# DrMcn.net
KiCad netlist of a schematic drawn in EAGLE
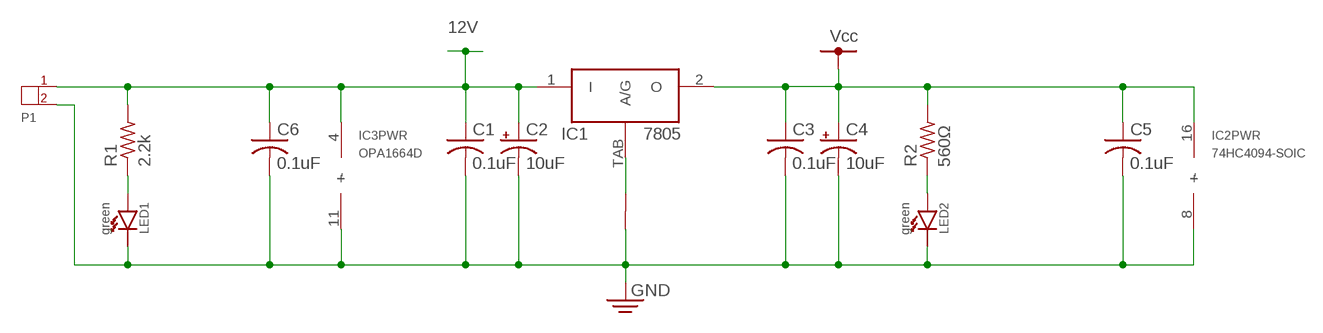
[diagram p0: schematic, sheet 1]
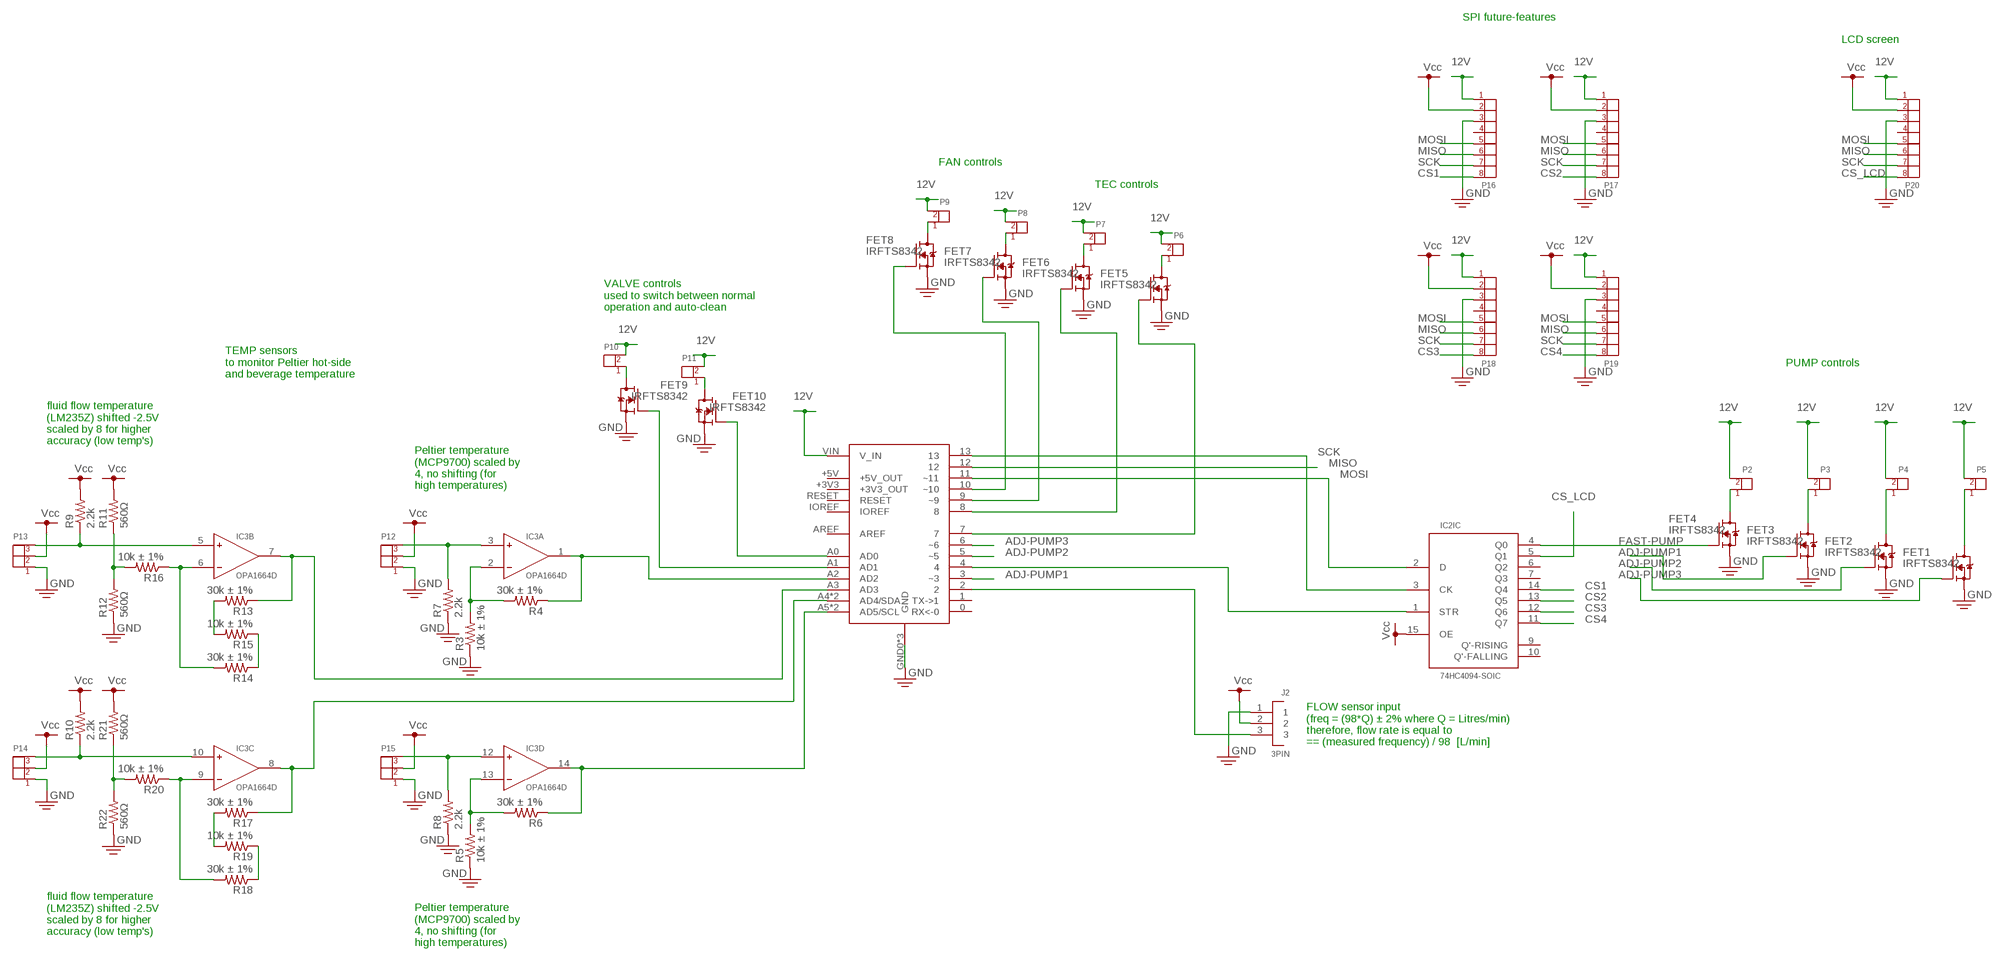
[diagram p1: schematic, sheet 2]

(export (version "E")
  (design (tool "Eeschema 10.0.6"))
  (components
    (comp (ref "-1")
      (value "SEPERATOR")
      (footprint "eagle-import:SEPERATOR")
      (libsource (lib "eagle-import") (part "SEPERATOR"))
    )
    (comp (ref "C1")
      (value "0.1uF")
      (footprint "eagle-import:C0805")
      (libsource (lib "eagle-import") (part "C-USC0805"))
    )
    (comp (ref "C2")
      (value "10uF")
      (footprint "eagle-import:E5-10,5")
      (libsource (lib "eagle-import") (part "CPOL-USE5-10.5"))
    )
    (comp (ref "C3")
      (value "0.1uF")
      (footprint "eagle-import:C0805")
      (libsource (lib "eagle-import") (part "C-USC0805"))
    )
    (comp (ref "C4")
      (value "10uF")
      (footprint "eagle-import:E5-10,5")
      (libsource (lib "eagle-import") (part "CPOL-USE5-10.5"))
    )
    (comp (ref "C5")
      (value "0.1uF")
      (footprint "eagle-import:C0805")
      (libsource (lib "eagle-import") (part "C-USC0805"))
    )
    (comp (ref "C6")
      (value "0.1uF")
      (footprint "eagle-import:C0805")
      (libsource (lib "eagle-import") (part "C-USC0805"))
    )
    (comp (ref "IC1")
      (value "7805")
      (footprint "eagle-import:TO-252")
      (libsource (lib "eagle-import") (part "7805"))
    )
    (comp (ref "IC2")
      (value "74HC4094-SOIC")
      (footprint "eagle-import:16-SOIC")
      (libsource (lib "eagle-import") (part "74HC4094-SOIC"))
    )
    (comp (ref "IC3")
      (value "OPA1664D")
      (footprint "eagle-import:14-SOP")
      (libsource (lib "eagle-import") (part "OPA1664D"))
    )
    (comp (ref "LED1")
      (value "green")
      (footprint "eagle-import:0603-LED")
      (libsource (lib "eagle-import") (part "LG_Q971"))
    )
    (comp (ref "LED2")
      (value "green")
      (footprint "eagle-import:0603-LED")
      (libsource (lib "eagle-import") (part "LG_Q971"))
    )
    (comp (ref "P1")
      (value "CONN-2P-VL")
      (footprint "eagle-import:B02P-VL")
      (libsource (lib "eagle-import") (part "CONN-2P-VL"))
    )
    (comp (ref "R1")
      (value "2.2k")
      (footprint "eagle-import:R0805")
      (libsource (lib "eagle-import") (part "R-US_R0805"))
    )
    (comp (ref "R2")
      (value "560Ω")
      (footprint "eagle-import:R0603")
      (libsource (lib "eagle-import") (part "R-US_R0603"))
    )
    (comp (ref "FET1")
      (value "IRFTS8342")
      (footprint "eagle-import:SOT23-6")
      (libsource (lib "eagle-import") (part "IRFTS8342"))
    )
    (comp (ref "FET2")
      (value "IRFTS8342")
      (footprint "eagle-import:SOT23-6")
      (libsource (lib "eagle-import") (part "IRFTS8342"))
    )
    (comp (ref "FET3")
      (value "IRFTS8342")
      (footprint "eagle-import:SOT23-6")
      (libsource (lib "eagle-import") (part "IRFTS8342"))
    )
    (comp (ref "FET4")
      (value "IRFTS8342")
      (footprint "eagle-import:SOT23-6")
      (libsource (lib "eagle-import") (part "IRFTS8342"))
    )
    (comp (ref "FET5")
      (value "IRFTS8342")
      (footprint "eagle-import:SOT23-6")
      (libsource (lib "eagle-import") (part "IRFTS8342"))
    )
    (comp (ref "FET6")
      (value "IRFTS8342")
      (footprint "eagle-import:SOT23-6")
      (libsource (lib "eagle-import") (part "IRFTS8342"))
    )
    (comp (ref "FET7")
      (value "IRFTS8342")
      (footprint "eagle-import:SOT23-6")
      (libsource (lib "eagle-import") (part "IRFTS8342"))
    )
    (comp (ref "FET8")
      (value "IRFTS8342")
      (footprint "eagle-import:SOT23-6")
      (libsource (lib "eagle-import") (part "IRFTS8342"))
    )
    (comp (ref "FET9")
      (value "IRFTS8342")
      (footprint "eagle-import:SOT23-6")
      (libsource (lib "eagle-import") (part "IRFTS8342"))
    )
    (comp (ref "FET10")
      (value "IRFTS8342")
      (footprint "eagle-import:SOT23-6")
      (libsource (lib "eagle-import") (part "IRFTS8342"))
    )
    (comp (ref "J1")
      (value "ARDUINO_UNO")
      (footprint "eagle-import:ARDUINO_UNO")
      (libsource (lib "eagle-import") (part "ARDUINO_UNO"))
    )
    (comp (ref "J2")
      (value "3PIN")
      (footprint "eagle-import:3P")
      (libsource (lib "eagle-import") (part "3PIN"))
    )
    (comp (ref "P2")
      (value "CONN-2P-PNI")
      (footprint "eagle-import:B02B-PNISK")
      (libsource (lib "eagle-import") (part "CONN-2P-PNI"))
    )
    (comp (ref "P3")
      (value "CONN-2P-PNI")
      (footprint "eagle-import:B02B-PNISK")
      (libsource (lib "eagle-import") (part "CONN-2P-PNI"))
    )
    (comp (ref "P4")
      (value "CONN-2P-PNI")
      (footprint "eagle-import:B02B-PNISK")
      (libsource (lib "eagle-import") (part "CONN-2P-PNI"))
    )
    (comp (ref "P5")
      (value "CONN-2P-PNI")
      (footprint "eagle-import:B02B-PNISK")
      (libsource (lib "eagle-import") (part "CONN-2P-PNI"))
    )
    (comp (ref "P6")
      (value "CONN-2P-VL")
      (footprint "eagle-import:B02P-VL")
      (libsource (lib "eagle-import") (part "CONN-2P-VL"))
    )
    (comp (ref "P7")
      (value "CONN-2P-VL")
      (footprint "eagle-import:B02P-VL")
      (libsource (lib "eagle-import") (part "CONN-2P-VL"))
    )
    (comp (ref "P8")
      (value "CONN-2P-PNI")
      (footprint "eagle-import:B02B-PNISK")
      (libsource (lib "eagle-import") (part "CONN-2P-PNI"))
    )
    (comp (ref "P9")
      (value "CONN-2P-PNI")
      (footprint "eagle-import:B02B-PNISK")
      (libsource (lib "eagle-import") (part "CONN-2P-PNI"))
    )
    (comp (ref "P10")
      (value "CONN-2P-PNI")
      (footprint "eagle-import:B02B-PNISK")
      (libsource (lib "eagle-import") (part "CONN-2P-PNI"))
    )
    (comp (ref "P11")
      (value "CONN-2P-PNI")
      (footprint "eagle-import:B02B-PNISK")
      (libsource (lib "eagle-import") (part "CONN-2P-PNI"))
    )
    (comp (ref "P12")
      (value "CONN-3P-PNI")
      (footprint "eagle-import:B03B-PNISK")
      (libsource (lib "eagle-import") (part "CONN-3P-PNI"))
    )
    (comp (ref "P13")
      (value "CONN-3P-PNI")
      (footprint "eagle-import:B03B-PNISK")
      (libsource (lib "eagle-import") (part "CONN-3P-PNI"))
    )
    (comp (ref "P14")
      (value "CONN-3P-PNI")
      (footprint "eagle-import:B03B-PNISK")
      (libsource (lib "eagle-import") (part "CONN-3P-PNI"))
    )
    (comp (ref "P15")
      (value "CONN-3P-PNI")
      (footprint "eagle-import:B03B-PNISK")
      (libsource (lib "eagle-import") (part "CONN-3P-PNI"))
    )
    (comp (ref "P16")
      (value "CONN-8P-PND")
      (footprint "eagle-import:B08B-PND")
      (libsource (lib "eagle-import") (part "CONN-8P-PND"))
    )
    (comp (ref "P17")
      (value "CONN-8P-PND")
      (footprint "eagle-import:B08B-PND")
      (libsource (lib "eagle-import") (part "CONN-8P-PND"))
    )
    (comp (ref "P18")
      (value "CONN-8P-PND")
      (footprint "eagle-import:B08B-PND")
      (libsource (lib "eagle-import") (part "CONN-8P-PND"))
    )
    (comp (ref "P19")
      (value "CONN-8P-PND")
      (footprint "eagle-import:B08B-PND")
      (libsource (lib "eagle-import") (part "CONN-8P-PND"))
    )
    (comp (ref "P20")
      (value "CONN-8P-PND")
      (footprint "eagle-import:B08B-PND")
      (libsource (lib "eagle-import") (part "CONN-8P-PND"))
    )
    (comp (ref "R3")
      (value "10k ± 1%")
      (footprint "eagle-import:R0603")
      (libsource (lib "eagle-import") (part "R-US_R0603"))
    )
    (comp (ref "R4")
      (value "30k ± 1%")
      (footprint "eagle-import:R0603")
      (libsource (lib "eagle-import") (part "R-US_R0603"))
    )
    (comp (ref "R5")
      (value "10k ± 1%")
      (footprint "eagle-import:R0603")
      (libsource (lib "eagle-import") (part "R-US_R0603"))
    )
    (comp (ref "R6")
      (value "30k ± 1%")
      (footprint "eagle-import:R0603")
      (libsource (lib "eagle-import") (part "R-US_R0603"))
    )
    (comp (ref "R7")
      (value "2.2k")
      (footprint "eagle-import:R0603")
      (libsource (lib "eagle-import") (part "R-US_R0603"))
    )
    (comp (ref "R8")
      (value "2.2k")
      (footprint "eagle-import:R0603")
      (libsource (lib "eagle-import") (part "R-US_R0603"))
    )
    (comp (ref "R9")
      (value "2.2k")
      (footprint "eagle-import:R0603")
      (libsource (lib "eagle-import") (part "R-US_R0603"))
    )
    (comp (ref "R10")
      (value "2.2k")
      (footprint "eagle-import:R0603")
      (libsource (lib "eagle-import") (part "R-US_R0603"))
    )
    (comp (ref "R11")
      (value "560Ω")
      (footprint "eagle-import:R0603")
      (libsource (lib "eagle-import") (part "R-US_R0603"))
    )
    (comp (ref "R12")
      (value "560Ω")
      (footprint "eagle-import:R0603")
      (libsource (lib "eagle-import") (part "R-US_R0603"))
    )
    (comp (ref "R13")
      (value "30k ± 1%")
      (footprint "eagle-import:R0603")
      (libsource (lib "eagle-import") (part "R-US_R0603"))
    )
    (comp (ref "R14")
      (value "30k ± 1%")
      (footprint "eagle-import:R0603")
      (libsource (lib "eagle-import") (part "R-US_R0603"))
    )
    (comp (ref "R15")
      (value "10k ± 1%")
      (footprint "eagle-import:R0603")
      (libsource (lib "eagle-import") (part "R-US_R0603"))
    )
    (comp (ref "R16")
      (value "10k ± 1%")
      (footprint "eagle-import:R0603")
      (libsource (lib "eagle-import") (part "R-US_R0603"))
    )
    (comp (ref "R17")
      (value "30k ± 1%")
      (footprint "eagle-import:R0603")
      (libsource (lib "eagle-import") (part "R-US_R0603"))
    )
    (comp (ref "R18")
      (value "30k ± 1%")
      (footprint "eagle-import:R0603")
      (libsource (lib "eagle-import") (part "R-US_R0603"))
    )
    (comp (ref "R19")
      (value "10k ± 1%")
      (footprint "eagle-import:R0603")
      (libsource (lib "eagle-import") (part "R-US_R0603"))
    )
    (comp (ref "R20")
      (value "10k ± 1%")
      (footprint "eagle-import:R0603")
      (libsource (lib "eagle-import") (part "R-US_R0603"))
    )
    (comp (ref "R21")
      (value "560Ω")
      (footprint "eagle-import:R0603")
      (libsource (lib "eagle-import") (part "R-US_R0603"))
    )
    (comp (ref "R22")
      (value "560Ω")
      (footprint "eagle-import:R0603")
      (libsource (lib "eagle-import") (part "R-US_R0603"))
    )
  )
  (nets
    (net (code "1") (name "12V") (class "Default")
      (node (ref "C1") (pin "1") (pinfunction "1_1") (pintype "passive"))
      (node (ref "C2") (pin "+") (pinfunction "+_+") (pintype "passive"))
      (node (ref "C6") (pin "1") (pinfunction "1_1") (pintype "passive"))
      (node (ref "IC1") (pin "1") (pinfunction "I_1") (pintype "bidirectional"))
      (node (ref "IC3") (pin "4") (pinfunction "+_4") (pintype "bidirectional"))
      (node (ref "J1") (pin "VIN") (pinfunction "V_IN_VIN") (pintype "bidirectional"))
      (node (ref "P1") (pin "1") (pinfunction "1_1") (pintype "bidirectional"))
      (node (ref "P10") (pin "2") (pinfunction "2_2") (pintype "bidirectional"))
      (node (ref "P11") (pin "2") (pinfunction "2_2") (pintype "bidirectional"))
      (node (ref "P16") (pin "1") (pinfunction "1_1") (pintype "bidirectional"))
      (node (ref "P17") (pin "1") (pinfunction "1_1") (pintype "bidirectional"))
      (node (ref "P18") (pin "1") (pinfunction "1_1") (pintype "bidirectional"))
      (node (ref "P19") (pin "1") (pinfunction "1_1") (pintype "bidirectional"))
      (node (ref "P2") (pin "2") (pinfunction "2_2") (pintype "bidirectional"))
      (node (ref "P20") (pin "1") (pinfunction "1_1") (pintype "bidirectional"))
      (node (ref "P3") (pin "2") (pinfunction "2_2") (pintype "bidirectional"))
      (node (ref "P4") (pin "2") (pinfunction "2_2") (pintype "bidirectional"))
      (node (ref "P5") (pin "2") (pinfunction "2_2") (pintype "bidirectional"))
      (node (ref "P6") (pin "2") (pinfunction "2_2") (pintype "bidirectional"))
      (node (ref "P7") (pin "2") (pinfunction "2_2") (pintype "bidirectional"))
      (node (ref "P8") (pin "2") (pinfunction "2_2") (pintype "bidirectional"))
      (node (ref "P9") (pin "2") (pinfunction "2_2") (pintype "bidirectional"))
      (node (ref "R1") (pin "2") (pinfunction "2_2") (pintype "passive"))
    )
    (net (code "2") (name "ADJ-PUMP1") (class "Default")
      (node (ref "FET3") (pin "3") (pinfunction "G_3") (pintype "passive"))
      (node (ref "J1") (pin "3") (pinfunction "~{3}_3") (pintype "bidirectional"))
    )
    (net (code "3") (name "ADJ-PUMP2") (class "Default")
      (node (ref "FET2") (pin "3") (pinfunction "G_3") (pintype "passive"))
      (node (ref "J1") (pin "5") (pinfunction "~{5}_5") (pintype "bidirectional"))
    )
    (net (code "4") (name "ADJ-PUMP3") (class "Default")
      (node (ref "FET1") (pin "3") (pinfunction "G_3") (pintype "passive"))
      (node (ref "J1") (pin "6") (pinfunction "~{6}_6") (pintype "bidirectional"))
    )
    (net (code "5") (name "CS1") (class "Default")
      (node (ref "IC2") (pin "14") (pinfunction "Q4_14") (pintype "bidirectional"))
      (node (ref "P16") (pin "8") (pinfunction "8_8") (pintype "bidirectional"))
    )
    (net (code "6") (name "CS2") (class "Default")
      (node (ref "IC2") (pin "13") (pinfunction "Q5_13") (pintype "bidirectional"))
      (node (ref "P17") (pin "8") (pinfunction "8_8") (pintype "bidirectional"))
    )
    (net (code "7") (name "CS3") (class "Default")
      (node (ref "IC2") (pin "12") (pinfunction "Q6_12") (pintype "bidirectional"))
      (node (ref "P18") (pin "8") (pinfunction "8_8") (pintype "bidirectional"))
    )
    (net (code "8") (name "CS4") (class "Default")
      (node (ref "IC2") (pin "11") (pinfunction "Q7_11") (pintype "bidirectional"))
      (node (ref "P19") (pin "8") (pinfunction "8_8") (pintype "bidirectional"))
    )
    (net (code "9") (name "CS_LCD") (class "Default")
      (node (ref "IC2") (pin "5") (pinfunction "Q1_5") (pintype "bidirectional"))
      (node (ref "P20") (pin "8") (pinfunction "8_8") (pintype "bidirectional"))
    )
    (net (code "10") (name "FAST-PUMP") (class "Default")
      (node (ref "FET4") (pin "3") (pinfunction "G_3") (pintype "passive"))
      (node (ref "IC2") (pin "4") (pinfunction "Q0_4") (pintype "bidirectional"))
    )
    (net (code "11") (name "GND") (class "Default")
      (node (ref "-1") (pin "P$1") (pinfunction "P$1_P$1") (pintype "bidirectional"))
      (node (ref "C1") (pin "2") (pinfunction "2_2") (pintype "passive"))
      (node (ref "C2") (pin "-") (pinfunction "-_-") (pintype "passive"))
      (node (ref "C3") (pin "2") (pinfunction "2_2") (pintype "passive"))
      (node (ref "C4") (pin "-") (pinfunction "-_-") (pintype "passive"))
      (node (ref "C5") (pin "2") (pinfunction "2_2") (pintype "passive"))
      (node (ref "C6") (pin "2") (pinfunction "2_2") (pintype "passive"))
      (node (ref "FET1") (pin "4") (pinfunction "S_4") (pintype "passive"))
      (node (ref "FET10") (pin "4") (pinfunction "S_4") (pintype "passive"))
      (node (ref "FET2") (pin "4") (pinfunction "S_4") (pintype "passive"))
      (node (ref "FET3") (pin "4") (pinfunction "S_4") (pintype "passive"))
      (node (ref "FET4") (pin "4") (pinfunction "S_4") (pintype "passive"))
      (node (ref "FET5") (pin "4") (pinfunction "S_4") (pintype "passive"))
      (node (ref "FET6") (pin "4") (pinfunction "S_4") (pintype "passive"))
      (node (ref "FET7") (pin "4") (pinfunction "S_4") (pintype "passive"))
      (node (ref "FET8") (pin "4") (pinfunction "S_4") (pintype "passive"))
      (node (ref "FET9") (pin "4") (pinfunction "S_4") (pintype "passive"))
      (node (ref "IC2") (pin "8") (pinfunction "-_8") (pintype "bidirectional"))
      (node (ref "IC3") (pin "11") (pinfunction "-_11") (pintype "bidirectional"))
      (node (ref "J1") (pin "GND0") (pinfunction "GND_GND0") (pintype "bidirectional"))
      (node (ref "J1") (pin "GND1") (pinfunction "GND_GND1") (pintype "bidirectional"))
      (node (ref "J1") (pin "GND2") (pinfunction "GND_GND2") (pintype "bidirectional"))
      (node (ref "J2") (pin "1") (pinfunction "1_1") (pintype "bidirectional"))
      (node (ref "LED1") (pin "C") (pinfunction "C_C") (pintype "bidirectional"))
      (node (ref "LED2") (pin "C") (pinfunction "C_C") (pintype "bidirectional"))
      (node (ref "P1") (pin "2") (pinfunction "2_2") (pintype "bidirectional"))
      (node (ref "P12") (pin "1") (pinfunction "1_1") (pintype "bidirectional"))
      (node (ref "P13") (pin "1") (pinfunction "1_1") (pintype "bidirectional"))
      (node (ref "P14") (pin "1") (pinfunction "1_1") (pintype "bidirectional"))
      (node (ref "P15") (pin "1") (pinfunction "1_1") (pintype "bidirectional"))
      (node (ref "P16") (pin "3") (pinfunction "3_3") (pintype "bidirectional"))
      (node (ref "P17") (pin "3") (pinfunction "3_3") (pintype "bidirectional"))
      (node (ref "P18") (pin "3") (pinfunction "3_3") (pintype "bidirectional"))
      (node (ref "P19") (pin "3") (pinfunction "3_3") (pintype "bidirectional"))
      (node (ref "P20") (pin "3") (pinfunction "3_3") (pintype "bidirectional"))
      (node (ref "R12") (pin "1") (pinfunction "1_1") (pintype "passive"))
      (node (ref "R22") (pin "1") (pinfunction "1_1") (pintype "passive"))
      (node (ref "R3") (pin "1") (pinfunction "1_1") (pintype "passive"))
      (node (ref "R5") (pin "1") (pinfunction "1_1") (pintype "passive"))
      (node (ref "R7") (pin "1") (pinfunction "1_1") (pintype "passive"))
      (node (ref "R8") (pin "1") (pinfunction "1_1") (pintype "passive"))
    )
    (net (code "12") (name "MISO") (class "Default")
      (node (ref "J1") (pin "12") (pinfunction "12_12") (pintype "bidirectional"))
      (node (ref "P16") (pin "6") (pinfunction "6_6") (pintype "bidirectional"))
      (node (ref "P17") (pin "6") (pinfunction "6_6") (pintype "bidirectional"))
      (node (ref "P18") (pin "6") (pinfunction "6_6") (pintype "bidirectional"))
      (node (ref "P19") (pin "6") (pinfunction "6_6") (pintype "bidirectional"))
      (node (ref "P20") (pin "6") (pinfunction "6_6") (pintype "bidirectional"))
    )
    (net (code "13") (name "MOSI") (class "Default")
      (node (ref "IC2") (pin "2") (pinfunction "D_2") (pintype "bidirectional"))
      (node (ref "J1") (pin "11") (pinfunction "~{11}_11") (pintype "bidirectional"))
      (node (ref "P16") (pin "5") (pinfunction "5_5") (pintype "bidirectional"))
      (node (ref "P17") (pin "5") (pinfunction "5_5") (pintype "bidirectional"))
      (node (ref "P18") (pin "5") (pinfunction "5_5") (pintype "bidirectional"))
      (node (ref "P19") (pin "5") (pinfunction "5_5") (pintype "bidirectional"))
      (node (ref "P20") (pin "5") (pinfunction "5_5") (pintype "bidirectional"))
    )
    (net (code "14") (name "Net-(FET1-D-Pad1)") (class "Default")
      (node (ref "FET1") (pin "1") (pinfunction "D_1") (pintype "passive"))
      (node (ref "FET1") (pin "2") (pinfunction "D_2") (pintype "passive"))
      (node (ref "FET1") (pin "5") (pinfunction "D_5") (pintype "passive"))
      (node (ref "FET1") (pin "6") (pinfunction "D_6") (pintype "passive"))
      (node (ref "P5") (pin "1") (pinfunction "1_1") (pintype "bidirectional"))
    )
    (net (code "15") (name "Net-(FET2-D-Pad1)") (class "Default")
      (node (ref "FET2") (pin "1") (pinfunction "D_1") (pintype "passive"))
      (node (ref "FET2") (pin "2") (pinfunction "D_2") (pintype "passive"))
      (node (ref "FET2") (pin "5") (pinfunction "D_5") (pintype "passive"))
      (node (ref "FET2") (pin "6") (pinfunction "D_6") (pintype "passive"))
      (node (ref "P4") (pin "1") (pinfunction "1_1") (pintype "bidirectional"))
    )
    (net (code "16") (name "Net-(FET3-D-Pad1)") (class "Default")
      (node (ref "FET3") (pin "1") (pinfunction "D_1") (pintype "passive"))
      (node (ref "FET3") (pin "2") (pinfunction "D_2") (pintype "passive"))
      (node (ref "FET3") (pin "5") (pinfunction "D_5") (pintype "passive"))
      (node (ref "FET3") (pin "6") (pinfunction "D_6") (pintype "passive"))
      (node (ref "P3") (pin "1") (pinfunction "1_1") (pintype "bidirectional"))
    )
    (net (code "17") (name "Net-(FET4-D-Pad1)") (class "Default")
      (node (ref "FET4") (pin "1") (pinfunction "D_1") (pintype "passive"))
      (node (ref "FET4") (pin "2") (pinfunction "D_2") (pintype "passive"))
      (node (ref "FET4") (pin "5") (pinfunction "D_5") (pintype "passive"))
      (node (ref "FET4") (pin "6") (pinfunction "D_6") (pintype "passive"))
      (node (ref "P2") (pin "1") (pinfunction "1_1") (pintype "bidirectional"))
    )
    (net (code "18") (name "Net-(FET5-D-Pad1)") (class "Default")
      (node (ref "FET5") (pin "1") (pinfunction "D_1") (pintype "passive"))
      (node (ref "FET5") (pin "2") (pinfunction "D_2") (pintype "passive"))
      (node (ref "FET5") (pin "5") (pinfunction "D_5") (pintype "passive"))
      (node (ref "FET5") (pin "6") (pinfunction "D_6") (pintype "passive"))
      (node (ref "P6") (pin "1") (pinfunction "1_1") (pintype "bidirectional"))
    )
    (net (code "19") (name "Net-(FET5-G)") (class "Default")
      (node (ref "FET5") (pin "3") (pinfunction "G_3") (pintype "passive"))
      (node (ref "J1") (pin "7") (pinfunction "7_7") (pintype "bidirectional"))
    )
    (net (code "20") (name "Net-(FET6-D-Pad1)") (class "Default")
      (node (ref "FET6") (pin "1") (pinfunction "D_1") (pintype "passive"))
      (node (ref "FET6") (pin "2") (pinfunction "D_2") (pintype "passive"))
      (node (ref "FET6") (pin "5") (pinfunction "D_5") (pintype "passive"))
      (node (ref "FET6") (pin "6") (pinfunction "D_6") (pintype "passive"))
      (node (ref "P7") (pin "1") (pinfunction "1_1") (pintype "bidirectional"))
    )
    (net (code "21") (name "Net-(FET6-G)") (class "Default")
      (node (ref "FET6") (pin "3") (pinfunction "G_3") (pintype "passive"))
      (node (ref "J1") (pin "8") (pinfunction "8_8") (pintype "bidirectional"))
    )
    (net (code "22") (name "Net-(FET7-D-Pad1)") (class "Default")
      (node (ref "FET7") (pin "1") (pinfunction "D_1") (pintype "passive"))
      (node (ref "FET7") (pin "2") (pinfunction "D_2") (pintype "passive"))
      (node (ref "FET7") (pin "5") (pinfunction "D_5") (pintype "passive"))
      (node (ref "FET7") (pin "6") (pinfunction "D_6") (pintype "passive"))
      (node (ref "P8") (pin "1") (pinfunction "1_1") (pintype "bidirectional"))
    )
    (net (code "23") (name "Net-(FET7-G)") (class "Default")
      (node (ref "FET7") (pin "3") (pinfunction "G_3") (pintype "passive"))
      (node (ref "J1") (pin "9") (pinfunction "~{9}_9") (pintype "bidirectional"))
    )
    (net (code "24") (name "Net-(FET8-D-Pad1)") (class "Default")
      (node (ref "FET8") (pin "1") (pinfunction "D_1") (pintype "passive"))
      (node (ref "FET8") (pin "2") (pinfunction "D_2") (pintype "passive"))
      (node (ref "FET8") (pin "5") (pinfunction "D_5") (pintype "passive"))
      (node (ref "FET8") (pin "6") (pinfunction "D_6") (pintype "passive"))
      (node (ref "P9") (pin "1") (pinfunction "1_1") (pintype "bidirectional"))
    )
    (net (code "25") (name "Net-(FET8-G)") (class "Default")
      (node (ref "FET8") (pin "3") (pinfunction "G_3") (pintype "passive"))
      (node (ref "J1") (pin "10") (pinfunction "~{10}_10") (pintype "bidirectional"))
    )
    (net (code "26") (name "Net-(FET9-D-Pad1)") (class "Default")
      (node (ref "FET9") (pin "1") (pinfunction "D_1") (pintype "passive"))
      (node (ref "FET9") (pin "2") (pinfunction "D_2") (pintype "passive"))
      (node (ref "FET9") (pin "5") (pinfunction "D_5") (pintype "passive"))
      (node (ref "FET9") (pin "6") (pinfunction "D_6") (pintype "passive"))
      (node (ref "P10") (pin "1") (pinfunction "1_1") (pintype "bidirectional"))
    )
    (net (code "27") (name "Net-(FET9-G)") (class "Default")
      (node (ref "FET9") (pin "3") (pinfunction "G_3") (pintype "passive"))
      (node (ref "J1") (pin "A1") (pinfunction "AD1_A1") (pintype "bidirectional"))
    )
    (net (code "28") (name "Net-(FET10-D-Pad1)") (class "Default")
      (node (ref "FET10") (pin "1") (pinfunction "D_1") (pintype "passive"))
      (node (ref "FET10") (pin "2") (pinfunction "D_2") (pintype "passive"))
      (node (ref "FET10") (pin "5") (pinfunction "D_5") (pintype "passive"))
      (node (ref "FET10") (pin "6") (pinfunction "D_6") (pintype "passive"))
      (node (ref "P11") (pin "1") (pinfunction "1_1") (pintype "bidirectional"))
    )
    (net (code "29") (name "Net-(FET10-G)") (class "Default")
      (node (ref "FET10") (pin "3") (pinfunction "G_3") (pintype "passive"))
      (node (ref "J1") (pin "A0") (pinfunction "AD0_A0") (pintype "bidirectional"))
    )
    (net (code "30") (name "Net-(IC1-A{slash}G)") (class "Default")
      (node (ref "-1") (pin "P$2") (pinfunction "P$2_P$2") (pintype "bidirectional"))
      (node (ref "IC1") (pin "TAB") (pinfunction "A/G_TAB") (pintype "bidirectional"))
    )
    (net (code "31") (name "Net-(IC2A-STR)") (class "Default")
      (node (ref "IC2") (pin "1") (pinfunction "STR_1") (pintype "bidirectional"))
      (node (ref "J1") (pin "4") (pinfunction "4_4") (pintype "bidirectional"))
    )
    (net (code "32") (name "Net-(IC3A-+)") (class "Default")
      (node (ref "IC3") (pin "3") (pinfunction "+_3") (pintype "bidirectional"))
      (node (ref "P12") (pin "3") (pinfunction "3_3") (pintype "bidirectional"))
      (node (ref "R7") (pin "2") (pinfunction "2_2") (pintype "passive"))
    )
    (net (code "33") (name "Net-(IC3A--)") (class "Default")
      (node (ref "IC3") (pin "2") (pinfunction "-_2") (pintype "bidirectional"))
      (node (ref "R3") (pin "2") (pinfunction "2_2") (pintype "passive"))
      (node (ref "R4") (pin "2") (pinfunction "2_2") (pintype "passive"))
    )
    (net (code "34") (name "Net-(IC3A-OUT)") (class "Default")
      (node (ref "IC3") (pin "1") (pinfunction "OUT_1") (pintype "bidirectional"))
      (node (ref "J1") (pin "A2") (pinfunction "AD2_A2") (pintype "bidirectional"))
      (node (ref "R4") (pin "1") (pinfunction "1_1") (pintype "passive"))
    )
    (net (code "35") (name "Net-(IC3B-+)") (class "Default")
      (node (ref "IC3") (pin "5") (pinfunction "+_5") (pintype "bidirectional"))
      (node (ref "P13") (pin "3") (pinfunction "3_3") (pintype "bidirectional"))
      (node (ref "R9") (pin "1") (pinfunction "1_1") (pintype "passive"))
    )
    (net (code "36") (name "Net-(IC3B--)") (class "Default")
      (node (ref "IC3") (pin "6") (pinfunction "-_6") (pintype "bidirectional"))
      (node (ref "R14") (pin "2") (pinfunction "2_2") (pintype "passive"))
      (node (ref "R16") (pin "1") (pinfunction "1_1") (pintype "passive"))
    )
    (net (code "37") (name "Net-(IC3B-OUT)") (class "Default")
      (node (ref "IC3") (pin "7") (pinfunction "OUT_7") (pintype "bidirectional"))
      (node (ref "J1") (pin "A3") (pinfunction "AD3_A3") (pintype "bidirectional"))
      (node (ref "R13") (pin "1") (pinfunction "1_1") (pintype "passive"))
    )
    (net (code "38") (name "Net-(IC3C-+)") (class "Default")
      (node (ref "IC3") (pin "10") (pinfunction "+_10") (pintype "bidirectional"))
      (node (ref "P14") (pin "3") (pinfunction "3_3") (pintype "bidirectional"))
      (node (ref "R10") (pin "1") (pinfunction "1_1") (pintype "passive"))
    )
    (net (code "39") (name "Net-(IC3C--)") (class "Default")
      (node (ref "IC3") (pin "9") (pinfunction "-_9") (pintype "bidirectional"))
      (node (ref "R18") (pin "2") (pinfunction "2_2") (pintype "passive"))
      (node (ref "R20") (pin "1") (pinfunction "1_1") (pintype "passive"))
    )
    (net (code "40") (name "Net-(IC3C-OUT)") (class "Default")
      (node (ref "IC3") (pin "8") (pinfunction "OUT_8") (pintype "bidirectional"))
      (node (ref "J1") (pin "A4") (pinfunction "AD4/SDA_A4") (pintype "bidirectional"))
      (node (ref "J1") (pin "SDA") (pinfunction "AD4/SDA_SDA") (pintype "bidirectional"))
      (node (ref "R17") (pin "1") (pinfunction "1_1") (pintype "passive"))
    )
    (net (code "41") (name "Net-(IC3D-+)") (class "Default")
      (node (ref "IC3") (pin "12") (pinfunction "+_12") (pintype "bidirectional"))
      (node (ref "P15") (pin "3") (pinfunction "3_3") (pintype "bidirectional"))
      (node (ref "R8") (pin "2") (pinfunction "2_2") (pintype "passive"))
    )
    (net (code "42") (name "Net-(IC3D--)") (class "Default")
      (node (ref "IC3") (pin "13") (pinfunction "-_13") (pintype "bidirectional"))
      (node (ref "R5") (pin "2") (pinfunction "2_2") (pintype "passive"))
      (node (ref "R6") (pin "2") (pinfunction "2_2") (pintype "passive"))
    )
    (net (code "43") (name "Net-(IC3D-OUT)") (class "Default")
      (node (ref "IC3") (pin "14") (pinfunction "OUT_14") (pintype "bidirectional"))
      (node (ref "J1") (pin "A5") (pinfunction "AD5/SCL_A5") (pintype "bidirectional"))
      (node (ref "J1") (pin "SCL") (pinfunction "AD5/SCL_SCL") (pintype "bidirectional"))
      (node (ref "R6") (pin "1") (pinfunction "1_1") (pintype "passive"))
    )
    (net (code "44") (name "Net-(J1-Pad2)") (class "Default")
      (node (ref "J1") (pin "2") (pinfunction "2_2") (pintype "bidirectional"))
      (node (ref "J2") (pin "3") (pinfunction "3_3") (pintype "bidirectional"))
    )
    (net (code "45") (name "Net-(LED1-PadA)") (class "Default")
      (node (ref "LED1") (pin "A") (pinfunction "A_A") (pintype "bidirectional"))
      (node (ref "R1") (pin "1") (pinfunction "1_1") (pintype "passive"))
    )
    (net (code "46") (name "Net-(LED2-PadA)") (class "Default")
      (node (ref "LED2") (pin "A") (pinfunction "A_A") (pintype "bidirectional"))
      (node (ref "R2") (pin "1") (pinfunction "1_1") (pintype "passive"))
    )
    (net (code "47") (name "Net-(R11-Pad1)") (class "Default")
      (node (ref "R11") (pin "1") (pinfunction "1_1") (pintype "passive"))
      (node (ref "R12") (pin "2") (pinfunction "2_2") (pintype "passive"))
      (node (ref "R16") (pin "2") (pinfunction "2_2") (pintype "passive"))
    )
    (net (code "48") (name "Net-(R13-Pad2)") (class "Default")
      (node (ref "R13") (pin "2") (pinfunction "2_2") (pintype "passive"))
      (node (ref "R15") (pin "2") (pinfunction "2_2") (pintype "passive"))
    )
    (net (code "49") (name "Net-(R14-Pad1)") (class "Default")
      (node (ref "R14") (pin "1") (pinfunction "1_1") (pintype "passive"))
      (node (ref "R15") (pin "1") (pinfunction "1_1") (pintype "passive"))
    )
    (net (code "50") (name "Net-(R17-Pad2)") (class "Default")
      (node (ref "R17") (pin "2") (pinfunction "2_2") (pintype "passive"))
      (node (ref "R19") (pin "2") (pinfunction "2_2") (pintype "passive"))
    )
    (net (code "51") (name "Net-(R18-Pad1)") (class "Default")
      (node (ref "R18") (pin "1") (pinfunction "1_1") (pintype "passive"))
      (node (ref "R19") (pin "1") (pinfunction "1_1") (pintype "passive"))
    )
    (net (code "52") (name "Net-(R20-Pad2)") (class "Default")
      (node (ref "R20") (pin "2") (pinfunction "2_2") (pintype "passive"))
      (node (ref "R21") (pin "1") (pinfunction "1_1") (pintype "passive"))
      (node (ref "R22") (pin "2") (pinfunction "2_2") (pintype "passive"))
    )
    (net (code "53") (name "SCK") (class "Default")
      (node (ref "IC2") (pin "3") (pinfunction "CK_3") (pintype "bidirectional"))
      (node (ref "J1") (pin "13") (pinfunction "13_13") (pintype "bidirectional"))
      (node (ref "P16") (pin "7") (pinfunction "7_7") (pintype "bidirectional"))
      (node (ref "P17") (pin "7") (pinfunction "7_7") (pintype "bidirectional"))
      (node (ref "P18") (pin "7") (pinfunction "7_7") (pintype "bidirectional"))
      (node (ref "P19") (pin "7") (pinfunction "7_7") (pintype "bidirectional"))
      (node (ref "P20") (pin "7") (pinfunction "7_7") (pintype "bidirectional"))
    )
    (net (code "54") (name "VCC") (class "Default")
      (node (ref "C3") (pin "1") (pinfunction "1_1") (pintype "passive"))
      (node (ref "C4") (pin "+") (pinfunction "+_+") (pintype "passive"))
      (node (ref "C5") (pin "1") (pinfunction "1_1") (pintype "passive"))
      (node (ref "IC1") (pin "2") (pinfunction "O_2") (pintype "bidirectional"))
      (node (ref "IC2") (pin "15") (pinfunction "OE_15") (pintype "bidirectional"))
      (node (ref "IC2") (pin "16") (pinfunction "+_16") (pintype "bidirectional"))
      (node (ref "J2") (pin "2") (pinfunction "2_2") (pintype "bidirectional"))
      (node (ref "P12") (pin "2") (pinfunction "2_2") (pintype "bidirectional"))
      (node (ref "P13") (pin "2") (pinfunction "2_2") (pintype "bidirectional"))
      (node (ref "P14") (pin "2") (pinfunction "2_2") (pintype "bidirectional"))
      (node (ref "P15") (pin "2") (pinfunction "2_2") (pintype "bidirectional"))
      (node (ref "P16") (pin "2") (pinfunction "2_2") (pintype "bidirectional"))
      (node (ref "P17") (pin "2") (pinfunction "2_2") (pintype "bidirectional"))
      (node (ref "P18") (pin "2") (pinfunction "2_2") (pintype "bidirectional"))
      (node (ref "P19") (pin "2") (pinfunction "2_2") (pintype "bidirectional"))
      (node (ref "P20") (pin "2") (pinfunction "2_2") (pintype "bidirectional"))
      (node (ref "R10") (pin "2") (pinfunction "2_2") (pintype "passive"))
      (node (ref "R11") (pin "2") (pinfunction "2_2") (pintype "passive"))
      (node (ref "R2") (pin "2") (pinfunction "2_2") (pintype "passive"))
      (node (ref "R21") (pin "2") (pinfunction "2_2") (pintype "passive"))
      (node (ref "R9") (pin "2") (pinfunction "2_2") (pintype "passive"))
    )
    (net (code "55") (name "unconnected-(IC2A-Q'-FALLING-Pad10)") (class "Default")
      (node (ref "IC2") (pin "10") (pinfunction "Q'-FALLING_10") (pintype "bidirectional"))
    )
    (net (code "56") (name "unconnected-(IC2A-Q'-RISING-Pad9)") (class "Default")
      (node (ref "IC2") (pin "9") (pinfunction "Q'-RISING_9") (pintype "bidirectional"))
    )
    (net (code "57") (name "unconnected-(IC2A-Q2-Pad6)") (class "Default")
      (node (ref "IC2") (pin "6") (pinfunction "Q2_6") (pintype "bidirectional"))
    )
    (net (code "58") (name "unconnected-(IC2A-Q3-Pad7)") (class "Default")
      (node (ref "IC2") (pin "7") (pinfunction "Q3_7") (pintype "bidirectional"))
    )
    (net (code "59") (name "unconnected-(J1-+3V3_OUT-Pad+3V3)") (class "Default")
      (node (ref "J1") (pin "+3V3") (pinfunction "+3V3_OUT_+3V3") (pintype "bidirectional"))
    )
    (net (code "60") (name "unconnected-(J1-+5V_OUT-Pad+5V)") (class "Default")
      (node (ref "J1") (pin "+5V") (pinfunction "+5V_OUT_+5V") (pintype "bidirectional"))
    )
    (net (code "61") (name "unconnected-(J1-PadAREF)") (class "Default")
      (node (ref "J1") (pin "AREF") (pinfunction "AREF_AREF") (pintype "bidirectional"))
    )
    (net (code "62") (name "unconnected-(J1-PadIOREF)") (class "Default")
      (node (ref "J1") (pin "IOREF") (pinfunction "IOREF_IOREF") (pintype "bidirectional"))
    )
    (net (code "63") (name "unconnected-(J1-PadRESET)") (class "Default")
      (node (ref "J1") (pin "RESET") (pinfunction "RESET_RESET") (pintype "bidirectional"))
    )
    (net (code "64") (name "unconnected-(J1-RX<-0-Pad0)") (class "Default")
      (node (ref "J1") (pin "0") (pinfunction "RX<-0_0") (pintype "bidirectional"))
    )
    (net (code "65") (name "unconnected-(J1-TX->1-Pad1)") (class "Default")
      (node (ref "J1") (pin "1") (pinfunction "TX->1_1") (pintype "bidirectional"))
    )
    (net (code "66") (name "unconnected-(P16-Pad4)") (class "Default")
      (node (ref "P16") (pin "4") (pinfunction "4_4") (pintype "bidirectional"))
    )
    (net (code "67") (name "unconnected-(P17-Pad4)") (class "Default")
      (node (ref "P17") (pin "4") (pinfunction "4_4") (pintype "bidirectional"))
    )
    (net (code "68") (name "unconnected-(P18-Pad4)") (class "Default")
      (node (ref "P18") (pin "4") (pinfunction "4_4") (pintype "bidirectional"))
    )
    (net (code "69") (name "unconnected-(P19-Pad4)") (class "Default")
      (node (ref "P19") (pin "4") (pinfunction "4_4") (pintype "bidirectional"))
    )
    (net (code "70") (name "unconnected-(P20-Pad4)") (class "Default")
      (node (ref "P20") (pin "4") (pinfunction "4_4") (pintype "bidirectional"))
    )
  )
)
